# Peripherals.net
KiCad netlist of a schematic drawn in Altium Designer
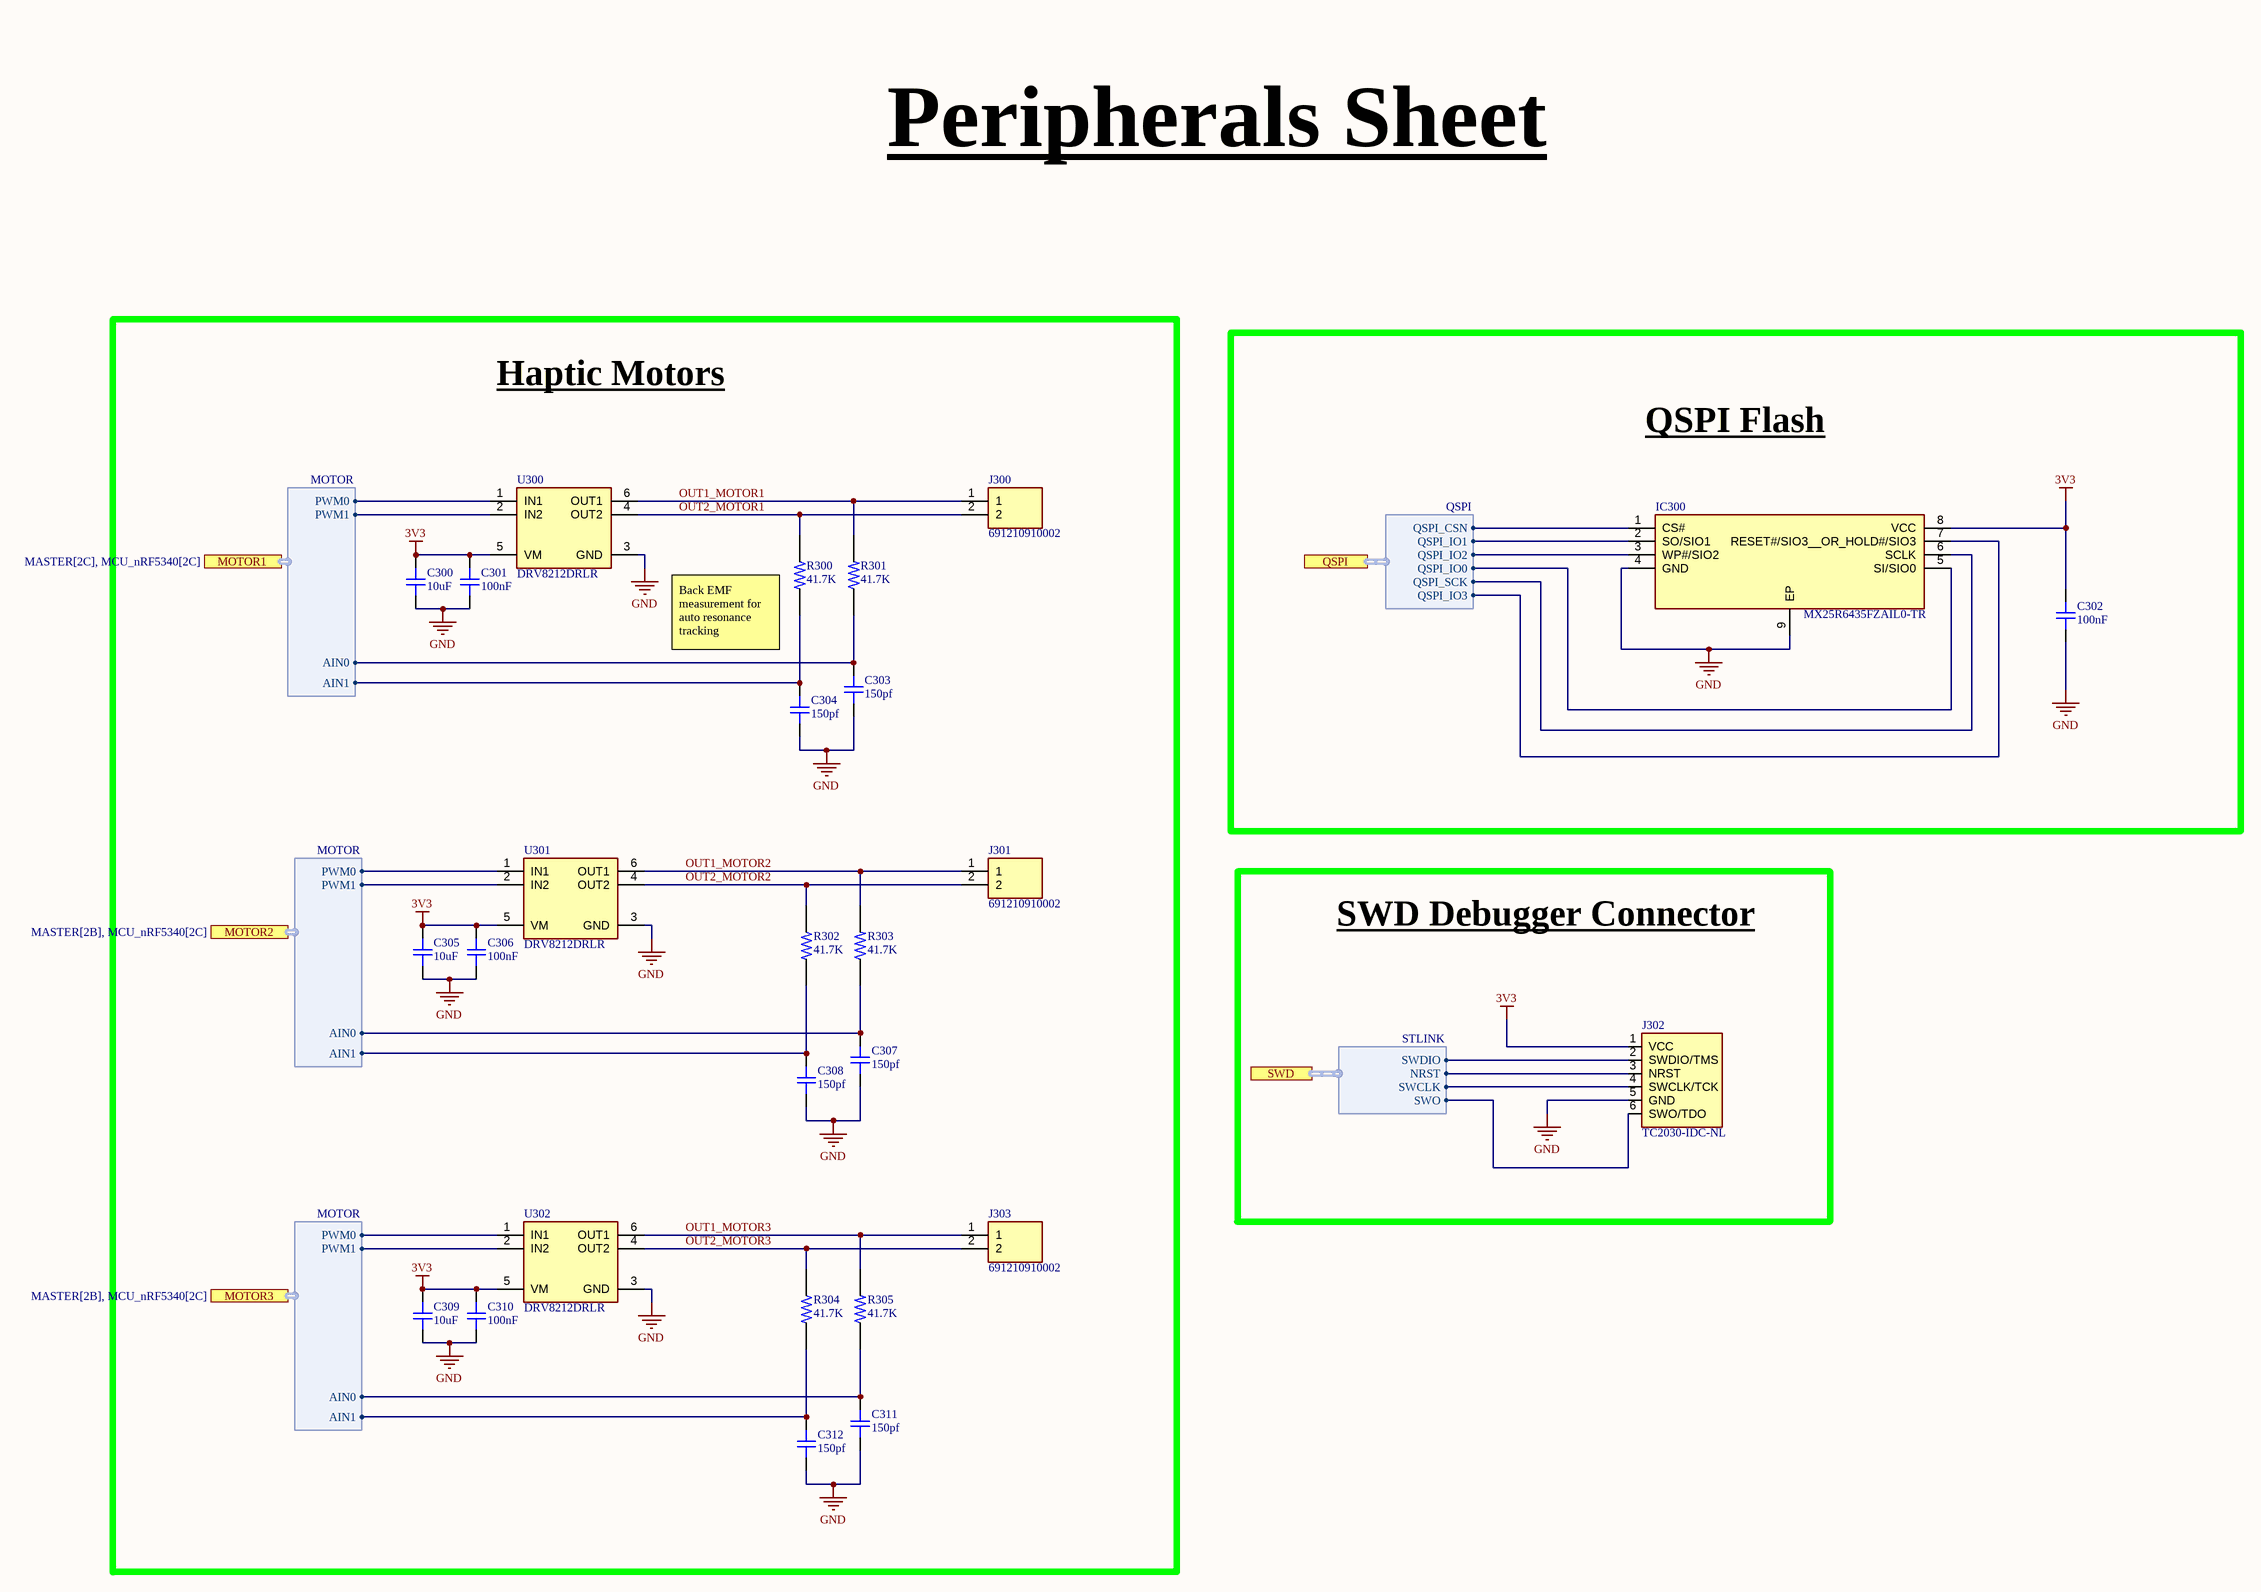
[diagram p0: Peripherals.SchDoc]

(export (version "E")
  (design (tool "Eeschema 10.0.6"))
  (components
    (comp (ref "C300")
      (value "10uF")
      (footprint "CAP_0603")
      (fields (field (name "TOLERANCE") "20%"))
      (libsource (lib "board") (part "CAP_0603"))
    )
    (comp (ref "C301")
      (value "100nF")
      (footprint "CAP_0603")
      (description "Capacitor SMD 0603")
      (libsource (lib "board") (part "CAP_0603"))
    )
    (comp (ref "C302")
      (value "100nF")
      (footprint "CAP_0603")
      (description "Capacitor SMD 0603")
      (libsource (lib "board") (part "CAP_0603"))
    )
    (comp (ref "C303")
      (value "150pf")
      (footprint "CAP_0603")
      (fields (field (name "TOLERANCE") "20%"))
      (libsource (lib "board") (part "CAP_0603"))
    )
    (comp (ref "C304")
      (value "150pf")
      (footprint "CAP_0603")
      (fields (field (name "TOLERANCE") "20%"))
      (libsource (lib "board") (part "CAP_0603"))
    )
    (comp (ref "C305")
      (value "10uF")
      (footprint "CAP_0603")
      (fields (field (name "TOLERANCE") "20%"))
      (libsource (lib "board") (part "CAP_0603"))
    )
    (comp (ref "C306")
      (value "100nF")
      (footprint "CAP_0603")
      (description "Capacitor SMD 0603")
      (libsource (lib "board") (part "CAP_0603"))
    )
    (comp (ref "C307")
      (value "150pf")
      (footprint "CAP_0603")
      (fields (field (name "TOLERANCE") "20%"))
      (libsource (lib "board") (part "CAP_0603"))
    )
    (comp (ref "C308")
      (value "150pf")
      (footprint "CAP_0603")
      (fields (field (name "TOLERANCE") "20%"))
      (libsource (lib "board") (part "CAP_0603"))
    )
    (comp (ref "C309")
      (value "10uF")
      (footprint "CAP_0603")
      (fields (field (name "TOLERANCE") "20%"))
      (libsource (lib "board") (part "CAP_0603"))
    )
    (comp (ref "C310")
      (value "100nF")
      (footprint "CAP_0603")
      (description "Capacitor SMD 0603")
      (libsource (lib "board") (part "CAP_0603"))
    )
    (comp (ref "C311")
      (value "150pf")
      (footprint "CAP_0603")
      (fields (field (name "TOLERANCE") "20%"))
      (libsource (lib "board") (part "CAP_0603"))
    )
    (comp (ref "C312")
      (value "150pf")
      (footprint "CAP_0603")
      (fields (field (name "TOLERANCE") "20%"))
      (libsource (lib "board") (part "CAP_0603"))
    )
    (comp (ref "IC300")
      (value "MX25R6435FZAIL0-TR")
      (footprint "SON80P400X400X60-9N")
      (description "Integrated Circuit")
      (fields (field (name "MOUSER PART NUMBER") "95-25R6435FZAIL0TR"))
      (libsource (lib "board") (part "MX25R6435FZAIL0-TR"))
    )
    (comp (ref "J300")
      (value "691210910002")
      (footprint "691210910002")
      (fields (field (name "MOUSER PART NUMBER") "710-691210910002"))
      (libsource (lib "board") (part "691210910002"))
    )
    (comp (ref "J301")
      (value "691210910002")
      (footprint "691210910002")
      (fields (field (name "MOUSER PART NUMBER") "710-691210910002"))
      (libsource (lib "board") (part "691210910002"))
    )
    (comp (ref "J302")
      (value "TC2030-IDC-NL")
      (footprint "TC2030IDC")
      (description "CABLE ADAPTER 6 POS")
      (libsource (lib "TC2030-IDC-NL") (part "TC2030-IDC-NL"))
    )
    (comp (ref "J303")
      (value "691210910002")
      (footprint "691210910002")
      (fields (field (name "MOUSER PART NUMBER") "710-691210910002"))
      (libsource (lib "board") (part "691210910002"))
    )
    (comp (ref "R300")
      (value "41.7K")
      (footprint "RESC1607X60N")
      (description "Res Thin Film 0402 41.7K Ohm 0.1% 1/16W 25ppm/C Molded SMD SMD Paper T/R")
      (fields (field (name "MF") "Yageo") (field (name "MP") "RC0603JR0710KL"))
      (libsource (lib "board") (part "RC0603JR0710KL"))
    )
    (comp (ref "R301")
      (value "41.7K")
      (footprint "RESC1607X60N")
      (description "Res Thin Film 0402 41.7K Ohm 0.1% 1/16W 25ppm/C Molded SMD SMD Paper T/R")
      (fields (field (name "MF") "Yageo") (field (name "MP") "RC0603JR0710KL"))
      (libsource (lib "board") (part "RC0603JR0710KL"))
    )
    (comp (ref "R302")
      (value "41.7K")
      (footprint "RESC1607X60N")
      (description "Res Thin Film 0402 41.7K Ohm 0.1% 1/16W 25ppm/C Molded SMD SMD Paper T/R")
      (fields (field (name "MF") "Yageo") (field (name "MP") "RC0603JR0710KL"))
      (libsource (lib "board") (part "RC0603JR0710KL"))
    )
    (comp (ref "R303")
      (value "41.7K")
      (footprint "RESC1607X60N")
      (description "Res Thin Film 0402 41.7K Ohm 0.1% 1/16W 25ppm/C Molded SMD SMD Paper T/R")
      (fields (field (name "MF") "Yageo") (field (name "MP") "RC0603JR0710KL"))
      (libsource (lib "board") (part "RC0603JR0710KL"))
    )
    (comp (ref "R304")
      (value "41.7K")
      (footprint "RESC1607X60N")
      (description "Res Thin Film 0402 41.7K Ohm 0.1% 1/16W 25ppm/C Molded SMD SMD Paper T/R")
      (fields (field (name "MF") "Yageo") (field (name "MP") "RC0603JR0710KL"))
      (libsource (lib "board") (part "RC0603JR0710KL"))
    )
    (comp (ref "R305")
      (value "41.7K")
      (footprint "RESC1607X60N")
      (description "Res Thin Film 0402 41.7K Ohm 0.1% 1/16W 25ppm/C Molded SMD SMD Paper T/R")
      (fields (field (name "MF") "Yageo") (field (name "MP") "RC0603JR0710KL"))
      (libsource (lib "board") (part "RC0603JR0710KL"))
    )
    (comp (ref "U300")
      (value "DRV8212DRLR")
      (footprint "SOTFL50P160X60-6N")
      (description "Motor / Motion / Ignition Controllers & Drivers 12-V, 2-A Low voltage H-bridge motor driver")
      (fields (field (name "MOUSER PART NUMBER") "595-DRV8212DRLR"))
      (libsource (lib "board") (part "DRV8212DRLR"))
    )
    (comp (ref "U301")
      (value "DRV8212DRLR")
      (footprint "SOTFL50P160X60-6N")
      (description "Motor / Motion / Ignition Controllers & Drivers 12-V, 2-A Low voltage H-bridge motor driver")
      (fields (field (name "MOUSER PART NUMBER") "595-DRV8212DRLR"))
      (libsource (lib "board") (part "DRV8212DRLR"))
    )
    (comp (ref "U302")
      (value "DRV8212DRLR")
      (footprint "SOTFL50P160X60-6N")
      (description "Motor / Motion / Ignition Controllers & Drivers 12-V, 2-A Low voltage H-bridge motor driver")
      (fields (field (name "MOUSER PART NUMBER") "595-DRV8212DRLR"))
      (libsource (lib "board") (part "DRV8212DRLR"))
    )
  )
  (nets
    (net (code "4") (name "/NRST") (class "Default")
      (node (ref "J302") (pin "3") (pinfunction "NRST_3") (pintype "passive"))
    )
    (net (code "5") (name "/OUT1_MOTOR1") (class "Default")
      (node (ref "J300") (pin "1") (pinfunction "1_1") (pintype "passive"))
      (node (ref "R301") (pin "2") (pinfunction "2_2") (pintype "passive"))
      (node (ref "U300") (pin "6") (pinfunction "OUT1_6") (pintype "passive"))
    )
    (net (code "6") (name "/OUT1_MOTOR2") (class "Default")
      (node (ref "J301") (pin "1") (pinfunction "1_1") (pintype "passive"))
      (node (ref "R303") (pin "2") (pinfunction "2_2") (pintype "passive"))
      (node (ref "U301") (pin "6") (pinfunction "OUT1_6") (pintype "passive"))
    )
    (net (code "7") (name "/OUT1_MOTOR3") (class "Default")
      (node (ref "J303") (pin "1") (pinfunction "1_1") (pintype "passive"))
      (node (ref "R305") (pin "2") (pinfunction "2_2") (pintype "passive"))
      (node (ref "U302") (pin "6") (pinfunction "OUT1_6") (pintype "passive"))
    )
    (net (code "8") (name "/OUT2_MOTOR1") (class "Default")
      (node (ref "J300") (pin "2") (pinfunction "2_2") (pintype "passive"))
      (node (ref "R300") (pin "1") (pinfunction "1_1") (pintype "passive"))
      (node (ref "U300") (pin "4") (pinfunction "OUT2_4") (pintype "passive"))
    )
    (net (code "9") (name "/OUT2_MOTOR2") (class "Default")
      (node (ref "J301") (pin "2") (pinfunction "2_2") (pintype "passive"))
      (node (ref "R302") (pin "1") (pinfunction "1_1") (pintype "passive"))
      (node (ref "U301") (pin "4") (pinfunction "OUT2_4") (pintype "passive"))
    )
    (net (code "10") (name "/OUT2_MOTOR3") (class "Default")
      (node (ref "J303") (pin "2") (pinfunction "2_2") (pintype "passive"))
      (node (ref "R304") (pin "1") (pinfunction "1_1") (pintype "passive"))
      (node (ref "U302") (pin "4") (pinfunction "OUT2_4") (pintype "passive"))
    )
    (net (code "11") (name "/QSPI_CSN") (class "Default")
      (node (ref "IC300") (pin "1") (pinfunction "CS#_1") (pintype "passive"))
    )
    (net (code "12") (name "/QSPI_IO0") (class "Default")
      (node (ref "IC300") (pin "5") (pinfunction "SI/SIO0_5") (pintype "passive"))
    )
    (net (code "13") (name "/QSPI_IO1") (class "Default")
      (node (ref "IC300") (pin "2") (pinfunction "SO/SIO1_2") (pintype "passive"))
    )
    (net (code "14") (name "/QSPI_IO2") (class "Default")
      (node (ref "IC300") (pin "3") (pinfunction "WP#/SIO2_3") (pintype "passive"))
    )
    (net (code "15") (name "/QSPI_IO3") (class "Default")
      (node (ref "IC300") (pin "7") (pinfunction "RESET#/SIO3__OR_HOLD#/SIO3_7") (pintype "passive"))
    )
    (net (code "16") (name "/QSPI_SCK") (class "Default")
      (node (ref "IC300") (pin "6") (pinfunction "SCLK_6") (pintype "passive"))
    )
    (net (code "17") (name "/SWCLK") (class "Default")
      (node (ref "J302") (pin "4") (pinfunction "SWCLK/TCK_4") (pintype "passive"))
    )
    (net (code "18") (name "/SWDIO") (class "Default")
      (node (ref "J302") (pin "2") (pinfunction "SWDIO/TMS_2") (pintype "passive"))
    )
    (net (code "19") (name "/SWO") (class "Default")
      (node (ref "J302") (pin "6") (pinfunction "SWO/TDO_6") (pintype "passive"))
    )
    (net (code "23") (name "3V3") (class "Default")
      (node (ref "C300") (pin "2") (pinfunction "2_2") (pintype "passive"))
      (node (ref "C301") (pin "2") (pinfunction "2_2") (pintype "passive"))
      (node (ref "C302") (pin "2") (pinfunction "2_2") (pintype "passive"))
      (node (ref "C305") (pin "2") (pinfunction "2_2") (pintype "passive"))
      (node (ref "C306") (pin "2") (pinfunction "2_2") (pintype "passive"))
      (node (ref "C309") (pin "2") (pinfunction "2_2") (pintype "passive"))
      (node (ref "C310") (pin "2") (pinfunction "2_2") (pintype "passive"))
      (node (ref "IC300") (pin "8") (pinfunction "VCC_8") (pintype "passive"))
      (node (ref "J302") (pin "1") (pinfunction "VCC_1") (pintype "passive"))
      (node (ref "U300") (pin "5") (pinfunction "VM_5") (pintype "passive"))
      (node (ref "U301") (pin "5") (pinfunction "VM_5") (pintype "passive"))
      (node (ref "U302") (pin "5") (pinfunction "VM_5") (pintype "passive"))
    )
    (net (code "24") (name "GND") (class "Default")
      (node (ref "C300") (pin "1") (pinfunction "1_1") (pintype "passive"))
      (node (ref "C301") (pin "1") (pinfunction "1_1") (pintype "passive"))
      (node (ref "C302") (pin "1") (pinfunction "1_1") (pintype "passive"))
      (node (ref "C303") (pin "1") (pinfunction "1_1") (pintype "passive"))
      (node (ref "C304") (pin "1") (pinfunction "1_1") (pintype "passive"))
      (node (ref "C305") (pin "1") (pinfunction "1_1") (pintype "passive"))
      (node (ref "C306") (pin "1") (pinfunction "1_1") (pintype "passive"))
      (node (ref "C307") (pin "1") (pinfunction "1_1") (pintype "passive"))
      (node (ref "C308") (pin "1") (pinfunction "1_1") (pintype "passive"))
      (node (ref "C309") (pin "1") (pinfunction "1_1") (pintype "passive"))
      (node (ref "C310") (pin "1") (pinfunction "1_1") (pintype "passive"))
      (node (ref "C311") (pin "1") (pinfunction "1_1") (pintype "passive"))
      (node (ref "C312") (pin "1") (pinfunction "1_1") (pintype "passive"))
      (node (ref "IC300") (pin "4") (pinfunction "GND_4") (pintype "passive"))
      (node (ref "IC300") (pin "9") (pinfunction "EP_9") (pintype "passive"))
      (node (ref "J302") (pin "5") (pinfunction "GND_5") (pintype "passive"))
      (node (ref "U300") (pin "3") (pinfunction "GND_3") (pintype "passive"))
      (node (ref "U301") (pin "3") (pinfunction "GND_3") (pintype "passive"))
      (node (ref "U302") (pin "3") (pinfunction "GND_3") (pintype "passive"))
    )
    (net (code "25") (name "Net-(C303-Pad2)") (class "Default")
      (node (ref "C303") (pin "2") (pinfunction "2_2") (pintype "passive"))
      (node (ref "R301") (pin "1") (pinfunction "1_1") (pintype "passive"))
    )
    (net (code "26") (name "Net-(C304-Pad2)") (class "Default")
      (node (ref "C304") (pin "2") (pinfunction "2_2") (pintype "passive"))
      (node (ref "R300") (pin "2") (pinfunction "2_2") (pintype "passive"))
    )
    (net (code "27") (name "Net-(C307-Pad2)") (class "Default")
      (node (ref "C307") (pin "2") (pinfunction "2_2") (pintype "passive"))
      (node (ref "R303") (pin "1") (pinfunction "1_1") (pintype "passive"))
    )
    (net (code "28") (name "Net-(C308-Pad2)") (class "Default")
      (node (ref "C308") (pin "2") (pinfunction "2_2") (pintype "passive"))
      (node (ref "R302") (pin "2") (pinfunction "2_2") (pintype "passive"))
    )
    (net (code "29") (name "Net-(C311-Pad2)") (class "Default")
      (node (ref "C311") (pin "2") (pinfunction "2_2") (pintype "passive"))
      (node (ref "R305") (pin "1") (pinfunction "1_1") (pintype "passive"))
    )
    (net (code "30") (name "Net-(C312-Pad2)") (class "Default")
      (node (ref "C312") (pin "2") (pinfunction "2_2") (pintype "passive"))
      (node (ref "R304") (pin "2") (pinfunction "2_2") (pintype "passive"))
    )
    (net (code "31") (name "unconnected-(U300-IN1-Pad1)") (class "Default")
      (node (ref "U300") (pin "1") (pinfunction "IN1_1") (pintype "passive"))
    )
    (net (code "32") (name "unconnected-(U300-IN2-Pad2)") (class "Default")
      (node (ref "U300") (pin "2") (pinfunction "IN2_2") (pintype "passive"))
    )
    (net (code "33") (name "unconnected-(U301-IN1-Pad1)") (class "Default")
      (node (ref "U301") (pin "1") (pinfunction "IN1_1") (pintype "passive"))
    )
    (net (code "34") (name "unconnected-(U301-IN2-Pad2)") (class "Default")
      (node (ref "U301") (pin "2") (pinfunction "IN2_2") (pintype "passive"))
    )
    (net (code "35") (name "unconnected-(U302-IN1-Pad1)") (class "Default")
      (node (ref "U302") (pin "1") (pinfunction "IN1_1") (pintype "passive"))
    )
    (net (code "36") (name "unconnected-(U302-IN2-Pad2)") (class "Default")
      (node (ref "U302") (pin "2") (pinfunction "IN2_2") (pintype "passive"))
    )
  )
)
